# Rail_Splitter.net
KiCad netlist of a schematic drawn in EAGLE
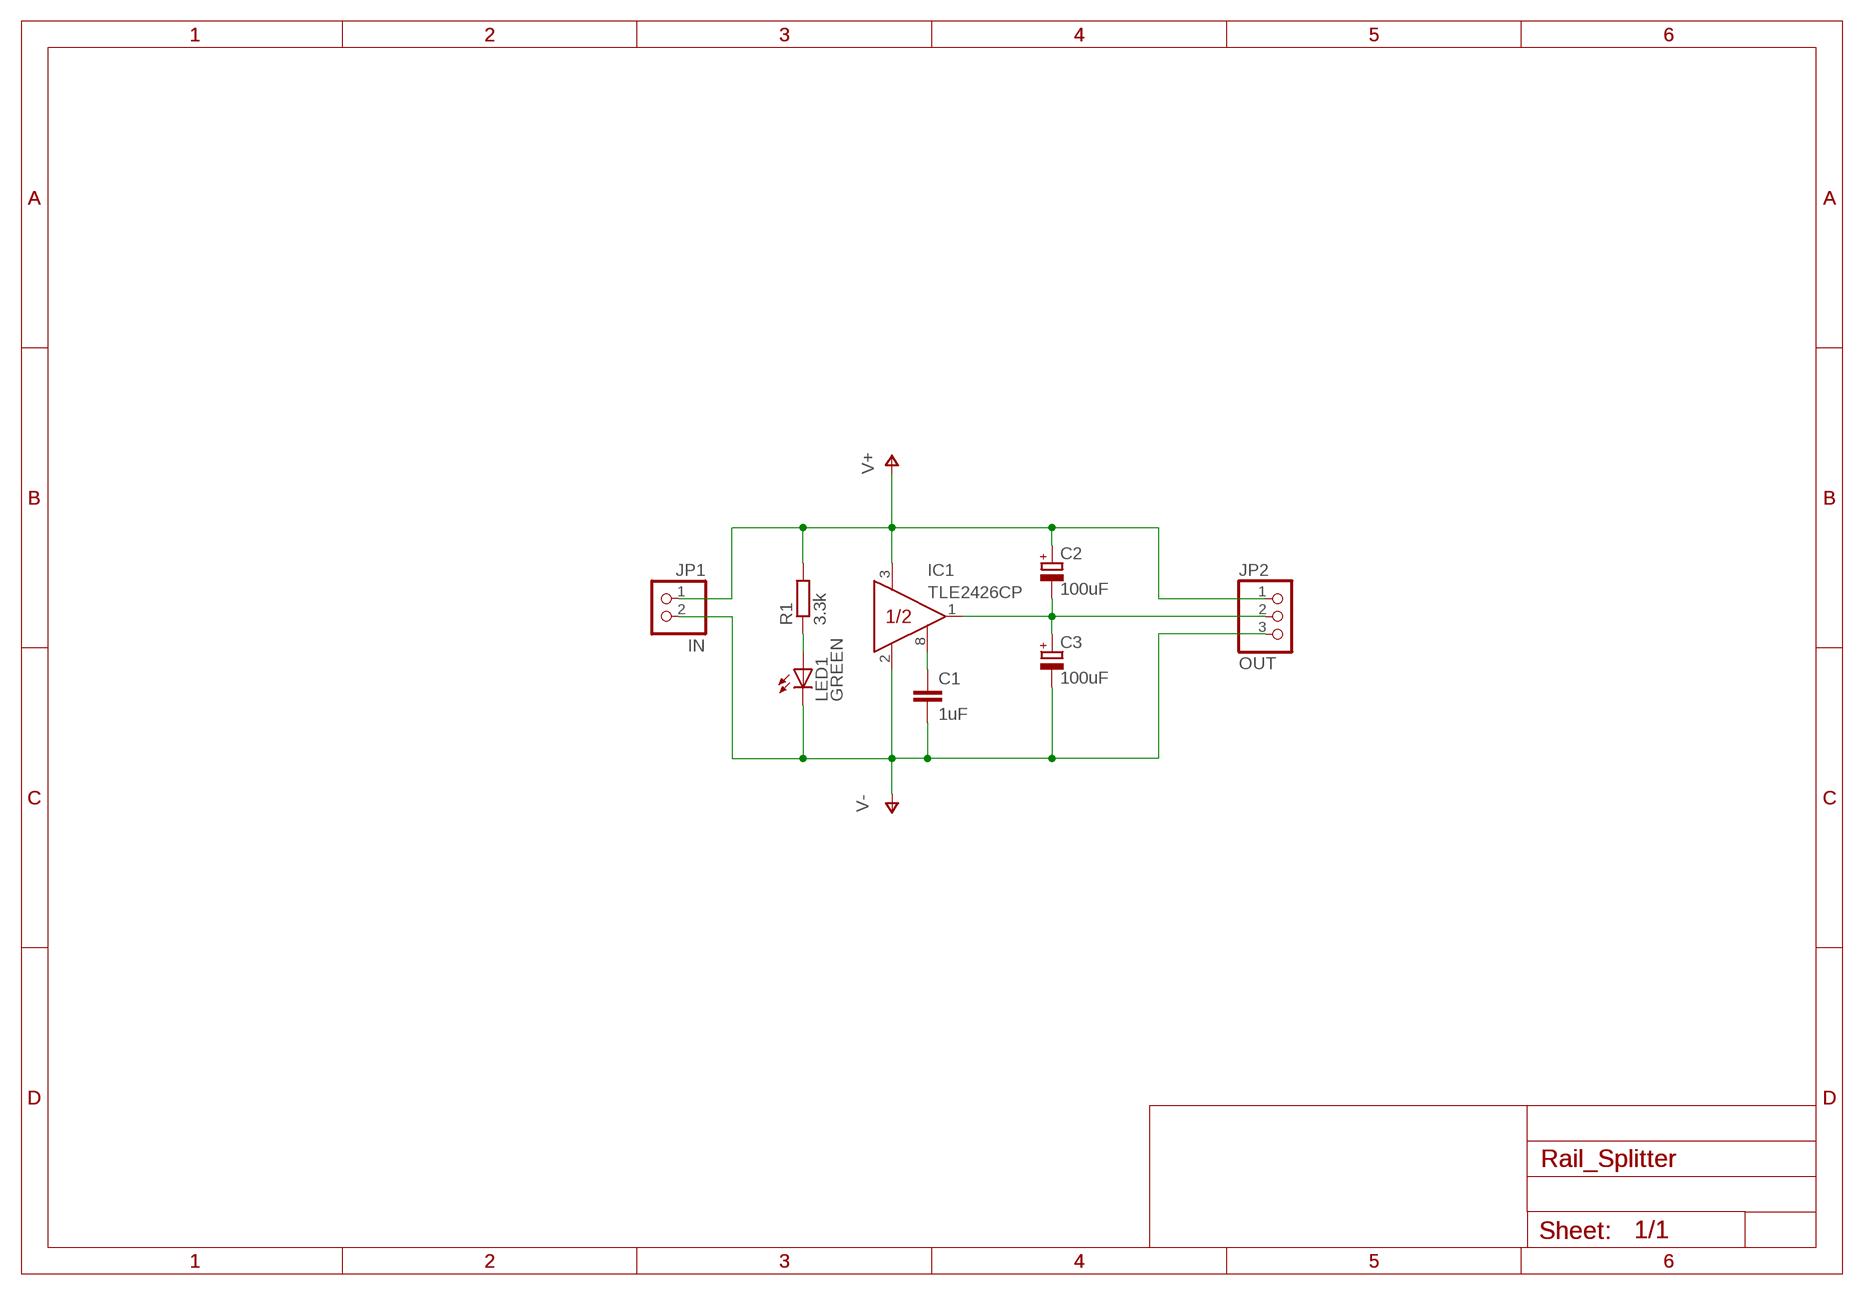
[diagram p0: schematic, sheet 1]

(export (version "E")
  (design (tool "Eeschema 10.0.6"))
  (components
    (comp (ref "C1")
      (value "1uF")
      (footprint "eagle-import:C050-035X075")
      (libsource (lib "eagle-import") (part "C-EU050-035X075"))
    )
    (comp (ref "C2")
      (value "100uF")
      (footprint "eagle-import:SANYO-OSCON_C6")
      (libsource (lib "eagle-import") (part "CPOL-EUSANYO_C6"))
    )
    (comp (ref "C3")
      (value "100uF")
      (footprint "eagle-import:SANYO-OSCON_C6")
      (libsource (lib "eagle-import") (part "CPOL-EUSANYO_C6"))
    )
    (comp (ref "IC1")
      (value "TLE2426CP")
      (footprint "eagle-import:DIP-8")
      (libsource (lib "eagle-import") (part "TLE2426PC"))
    )
    (comp (ref "JP1")
      (value "IN")
      (footprint "eagle-import:1X02")
      (libsource (lib "eagle-import") (part "PINHD-1X2"))
    )
    (comp (ref "JP2")
      (value "OUT")
      (footprint "eagle-import:1X03")
      (libsource (lib "eagle-import") (part "PINHD-1X3"))
    )
    (comp (ref "LED1")
      (value "GREEN")
      (footprint "eagle-import:LED3MM")
      (libsource (lib "eagle-import") (part "LED3MM"))
    )
    (comp (ref "R1")
      (value "3.3k")
      (footprint "eagle-import:0207_7")
      (libsource (lib "eagle-import") (part "R-EU_0207/7"))
    )
  )
  (nets
    (net (code "1") (name "Net-(IC1-NR)") (class "Default")
      (node (ref "C1") (pin "1") (pinfunction "1_1") (pintype "passive"))
      (node (ref "IC1") (pin "8") (pinfunction "NR_8") (pintype "passive"))
    )
    (net (code "2") (name "Net-(IC1-OUT)") (class "Default")
      (node (ref "C2") (pin "-") (pinfunction "-_-") (pintype "passive"))
      (node (ref "C3") (pin "+") (pinfunction "+_+") (pintype "passive"))
      (node (ref "IC1") (pin "1") (pinfunction "OUT_1") (pintype "passive"))
      (node (ref "JP2") (pin "2") (pinfunction "2_2") (pintype "passive"))
    )
    (net (code "3") (name "Net-(LED1-PadA)") (class "Default")
      (node (ref "LED1") (pin "A") (pinfunction "A_A") (pintype "passive"))
      (node (ref "R1") (pin "1") (pinfunction "1_1") (pintype "passive"))
    )
    (net (code "4") (name "V+") (class "Default")
      (node (ref "C2") (pin "+") (pinfunction "+_+") (pintype "passive"))
      (node (ref "IC1") (pin "3") (pinfunction "IN_3") (pintype "passive"))
      (node (ref "JP1") (pin "1") (pinfunction "1_1") (pintype "passive"))
      (node (ref "JP2") (pin "1") (pinfunction "1_1") (pintype "passive"))
      (node (ref "R1") (pin "2") (pinfunction "2_2") (pintype "passive"))
    )
    (net (code "5") (name "V-") (class "Default")
      (node (ref "C1") (pin "2") (pinfunction "2_2") (pintype "passive"))
      (node (ref "C3") (pin "-") (pinfunction "-_-") (pintype "passive"))
      (node (ref "IC1") (pin "2") (pinfunction "COM_2") (pintype "passive"))
      (node (ref "JP1") (pin "2") (pinfunction "2_2") (pintype "passive"))
      (node (ref "JP2") (pin "3") (pinfunction "3_3") (pintype "passive"))
      (node (ref "LED1") (pin "K") (pinfunction "C_K") (pintype "passive"))
    )
  )
)
